# Coleco_Cart_V4.net
KiCad netlist of a schematic drawn in EAGLE
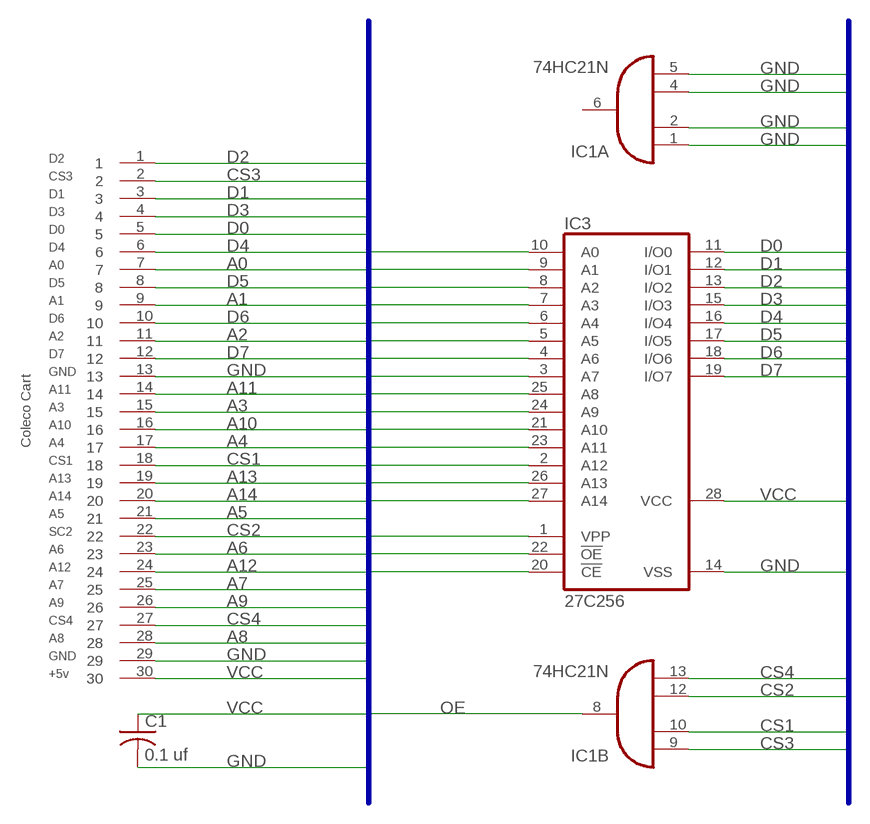
[diagram p0: schematic, sheet 1]

(export (version "E")
  (design (tool "Eeschema 10.0.6"))
  (components
    (comp (ref "C1")
      (value "0.1 uf")
      (footprint "eagle-import:C050-030X075")
      (libsource (lib "eagle-import") (part "C-US050-030X075"))
    )
    (comp (ref "IC1")
      (value "74HC21N")
      (footprint "eagle-import:DIL14")
      (libsource (lib "eagle-import") (part "7421NHC"))
    )
    (comp (ref "IC3")
      (value "27C256")
      (footprint "eagle-import:DIL28-6")
      (libsource (lib "eagle-import") (part "27C256AG"))
    )
    (comp (ref "U$1")
      (value "CART")
      (footprint "eagle-import:CART")
      (libsource (lib "eagle-import") (part "CART"))
    )
  )
  (nets
    (net (code "1") (name "/A0") (class "Default")
      (node (ref "IC3") (pin "10") (pinfunction "A0_10") (pintype "input"))
      (node (ref "U$1") (pin "7") (pinfunction "7_7") (pintype "bidirectional"))
    )
    (net (code "2") (name "/A1") (class "Default")
      (node (ref "IC3") (pin "9") (pinfunction "A1_9") (pintype "input"))
      (node (ref "U$1") (pin "9") (pinfunction "9_9") (pintype "bidirectional"))
    )
    (net (code "3") (name "/A2") (class "Default")
      (node (ref "IC3") (pin "8") (pinfunction "A2_8") (pintype "input"))
      (node (ref "U$1") (pin "11") (pinfunction "11_11") (pintype "bidirectional"))
    )
    (net (code "4") (name "/A3") (class "Default")
      (node (ref "IC3") (pin "7") (pinfunction "A3_7") (pintype "input"))
      (node (ref "U$1") (pin "15") (pinfunction "15_15") (pintype "bidirectional"))
    )
    (net (code "5") (name "/A4") (class "Default")
      (node (ref "IC3") (pin "6") (pinfunction "A4_6") (pintype "input"))
      (node (ref "U$1") (pin "17") (pinfunction "17_17") (pintype "bidirectional"))
    )
    (net (code "6") (name "/A5") (class "Default")
      (node (ref "IC3") (pin "5") (pinfunction "A5_5") (pintype "input"))
      (node (ref "U$1") (pin "21") (pinfunction "21_21") (pintype "bidirectional"))
    )
    (net (code "7") (name "/A6") (class "Default")
      (node (ref "IC3") (pin "4") (pinfunction "A6_4") (pintype "input"))
      (node (ref "U$1") (pin "23") (pinfunction "23_23") (pintype "bidirectional"))
    )
    (net (code "8") (name "/A7") (class "Default")
      (node (ref "IC3") (pin "3") (pinfunction "A7_3") (pintype "input"))
      (node (ref "U$1") (pin "25") (pinfunction "25_25") (pintype "bidirectional"))
    )
    (net (code "9") (name "/A8") (class "Default")
      (node (ref "IC3") (pin "25") (pinfunction "A8_25") (pintype "input"))
      (node (ref "U$1") (pin "28") (pinfunction "28_28") (pintype "bidirectional"))
    )
    (net (code "10") (name "/A9") (class "Default")
      (node (ref "IC3") (pin "24") (pinfunction "A9_24") (pintype "input"))
      (node (ref "U$1") (pin "26") (pinfunction "26_26") (pintype "bidirectional"))
    )
    (net (code "11") (name "/A10") (class "Default")
      (node (ref "IC3") (pin "21") (pinfunction "A10_21") (pintype "input"))
      (node (ref "U$1") (pin "16") (pinfunction "16_16") (pintype "bidirectional"))
    )
    (net (code "12") (name "/A11") (class "Default")
      (node (ref "IC3") (pin "23") (pinfunction "A11_23") (pintype "input"))
      (node (ref "U$1") (pin "14") (pinfunction "14_14") (pintype "bidirectional"))
    )
    (net (code "13") (name "/A12") (class "Default")
      (node (ref "IC3") (pin "2") (pinfunction "A12_2") (pintype "input"))
      (node (ref "U$1") (pin "24") (pinfunction "24_24") (pintype "bidirectional"))
    )
    (net (code "14") (name "/A13") (class "Default")
      (node (ref "IC3") (pin "26") (pinfunction "A13_26") (pintype "input"))
      (node (ref "U$1") (pin "19") (pinfunction "19_19") (pintype "bidirectional"))
    )
    (net (code "15") (name "/A14") (class "Default")
      (node (ref "IC3") (pin "27") (pinfunction "A14_27") (pintype "input"))
      (node (ref "U$1") (pin "20") (pinfunction "20_20") (pintype "bidirectional"))
    )
    (net (code "16") (name "/CS1") (class "Default")
      (node (ref "IC1") (pin "10") (pinfunction "I1_10") (pintype "input"))
      (node (ref "U$1") (pin "18") (pinfunction "18_18") (pintype "bidirectional"))
    )
    (net (code "17") (name "/CS2") (class "Default")
      (node (ref "IC1") (pin "12") (pinfunction "I2_12") (pintype "input"))
      (node (ref "U$1") (pin "22") (pinfunction "22_22") (pintype "bidirectional"))
    )
    (net (code "18") (name "/CS3") (class "Default")
      (node (ref "IC1") (pin "9") (pinfunction "I0_9") (pintype "input"))
      (node (ref "U$1") (pin "2") (pinfunction "2_2") (pintype "bidirectional"))
    )
    (net (code "19") (name "/CS4") (class "Default")
      (node (ref "IC1") (pin "13") (pinfunction "I3_13") (pintype "input"))
      (node (ref "U$1") (pin "27") (pinfunction "27_27") (pintype "bidirectional"))
    )
    (net (code "20") (name "/D0") (class "Default")
      (node (ref "IC3") (pin "11") (pinfunction "I/O0_11") (pintype "tri_state"))
      (node (ref "U$1") (pin "5") (pinfunction "5_5") (pintype "bidirectional"))
    )
    (net (code "21") (name "/D1") (class "Default")
      (node (ref "IC3") (pin "12") (pinfunction "I/O1_12") (pintype "tri_state"))
      (node (ref "U$1") (pin "3") (pinfunction "3_3") (pintype "bidirectional"))
    )
    (net (code "22") (name "/D2") (class "Default")
      (node (ref "IC3") (pin "13") (pinfunction "I/O2_13") (pintype "tri_state"))
      (node (ref "U$1") (pin "1") (pinfunction "1_1") (pintype "bidirectional"))
    )
    (net (code "23") (name "/D3") (class "Default")
      (node (ref "IC3") (pin "15") (pinfunction "I/O3_15") (pintype "tri_state"))
      (node (ref "U$1") (pin "4") (pinfunction "4_4") (pintype "bidirectional"))
    )
    (net (code "24") (name "/D4") (class "Default")
      (node (ref "IC3") (pin "16") (pinfunction "I/O4_16") (pintype "tri_state"))
      (node (ref "U$1") (pin "6") (pinfunction "6_6") (pintype "bidirectional"))
    )
    (net (code "25") (name "/D5") (class "Default")
      (node (ref "IC3") (pin "17") (pinfunction "I/O5_17") (pintype "tri_state"))
      (node (ref "U$1") (pin "8") (pinfunction "8_8") (pintype "bidirectional"))
    )
    (net (code "26") (name "/D6") (class "Default")
      (node (ref "IC3") (pin "18") (pinfunction "I/O6_18") (pintype "tri_state"))
      (node (ref "U$1") (pin "10") (pinfunction "10_10") (pintype "bidirectional"))
    )
    (net (code "27") (name "/D7") (class "Default")
      (node (ref "IC3") (pin "19") (pinfunction "I/O7_19") (pintype "tri_state"))
      (node (ref "U$1") (pin "12") (pinfunction "12_12") (pintype "bidirectional"))
    )
    (net (code "28") (name "/GND") (class "Default")
      (node (ref "C1") (pin "2") (pinfunction "2_2") (pintype "passive"))
      (node (ref "IC1") (pin "1") (pinfunction "I0_1") (pintype "input"))
      (node (ref "IC1") (pin "2") (pinfunction "I1_2") (pintype "input"))
      (node (ref "IC1") (pin "4") (pinfunction "I2_4") (pintype "input"))
      (node (ref "IC1") (pin "5") (pinfunction "I3_5") (pintype "input"))
      (node (ref "IC3") (pin "14") (pinfunction "VSS_14") (pintype "power_in"))
      (node (ref "U$1") (pin "13") (pinfunction "13_13") (pintype "power_in"))
      (node (ref "U$1") (pin "29") (pinfunction "29_29") (pintype "power_in"))
    )
    (net (code "29") (name "/OE") (class "Default")
      (node (ref "IC1") (pin "8") (pinfunction "O_8") (pintype "output"))
      (node (ref "IC3") (pin "20") (pinfunction "~{CE}_20") (pintype "input"))
      (node (ref "IC3") (pin "22") (pinfunction "~{OE}_22") (pintype "input"))
    )
    (net (code "30") (name "/VCC") (class "Default")
      (node (ref "C1") (pin "1") (pinfunction "1_1") (pintype "passive"))
      (node (ref "IC3") (pin "1") (pinfunction "VPP_1") (pintype "input"))
      (node (ref "IC3") (pin "28") (pinfunction "VCC_28") (pintype "power_in"))
      (node (ref "U$1") (pin "30") (pinfunction "30_30") (pintype "power_in"))
    )
    (net (code "31") (name "unconnected-(IC1A-O-Pad6)") (class "Default")
      (node (ref "IC1") (pin "6") (pinfunction "O_6") (pintype "output"))
    )
  )
)
